# SprayController.net
KiCad netlist of a schematic drawn in EAGLE
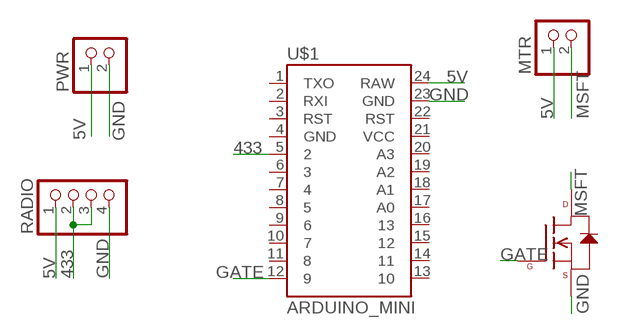
[diagram p0: schematic, sheet 1]

(export (version "E")
  (design (tool "Eeschema 10.0.6"))
  (components
    (comp (ref "MTR")
      (value "PINHD-1X2/90")
      (footprint "eagle-import:1X02_90")
      (libsource (lib "eagle-import") (part "PINHD-1X2/90"))
    )
    (comp (ref "PWR")
      (value "PINHD-1X2/90")
      (footprint "eagle-import:1X02_90")
      (libsource (lib "eagle-import") (part "PINHD-1X2/90"))
    )
    (comp (ref "Q1")
      (value "N-CHANNEL-MOSFET-BSS138")
      (footprint "eagle-import:SOT23-3")
      (libsource (lib "eagle-import") (part "N-CHANNEL-MOSFET-BSS138"))
    )
    (comp (ref "RADIO")
      (value "PINHD-1X4/90")
      (footprint "eagle-import:1X04_90")
      (libsource (lib "eagle-import") (part "PINHD-1X4/90"))
    )
    (comp (ref "U$1")
      (value "ARDUINO_MINI")
      (footprint "eagle-import:ARDUINO_MINI")
      (libsource (lib "eagle-import") (part "ARDUINO_MINI"))
    )
  )
  (nets
    (net (code "1") (name "/5V") (class "Default")
      (node (ref "MTR") (pin "1") (pinfunction "1_1") (pintype "passive"))
      (node (ref "PWR") (pin "1") (pinfunction "1_1") (pintype "passive"))
      (node (ref "RADIO") (pin "1") (pinfunction "1_1") (pintype "passive"))
      (node (ref "U$1") (pin "24") (pinfunction "RAW_24") (pintype "bidirectional"))
    )
    (net (code "2") (name "/433") (class "Default")
      (node (ref "RADIO") (pin "2") (pinfunction "2_2") (pintype "passive"))
      (node (ref "RADIO") (pin "3") (pinfunction "3_3") (pintype "passive"))
      (node (ref "U$1") (pin "5") (pinfunction "2_5") (pintype "bidirectional"))
    )
    (net (code "3") (name "/GATE") (class "Default")
      (node (ref "Q1") (pin "1") (pinfunction "G_1") (pintype "passive"))
      (node (ref "U$1") (pin "12") (pinfunction "9_12") (pintype "bidirectional"))
    )
    (net (code "4") (name "/GND") (class "Default")
      (node (ref "PWR") (pin "2") (pinfunction "2_2") (pintype "passive"))
      (node (ref "Q1") (pin "2") (pinfunction "S_2") (pintype "passive"))
      (node (ref "RADIO") (pin "4") (pinfunction "4_4") (pintype "passive"))
      (node (ref "U$1") (pin "23") (pinfunction "GND_23") (pintype "bidirectional"))
    )
    (net (code "5") (name "/MSFT") (class "Default")
      (node (ref "MTR") (pin "2") (pinfunction "2_2") (pintype "passive"))
      (node (ref "Q1") (pin "3") (pinfunction "D_3") (pintype "passive"))
    )
    (net (code "6") (name "unconnected-(U$1-3-Pad6)") (class "Default")
      (node (ref "U$1") (pin "6") (pinfunction "3_6") (pintype "bidirectional"))
    )
    (net (code "7") (name "unconnected-(U$1-4-Pad7)") (class "Default")
      (node (ref "U$1") (pin "7") (pinfunction "4_7") (pintype "bidirectional"))
    )
    (net (code "8") (name "unconnected-(U$1-5-Pad8)") (class "Default")
      (node (ref "U$1") (pin "8") (pinfunction "5_8") (pintype "bidirectional"))
    )
    (net (code "9") (name "unconnected-(U$1-6-Pad9)") (class "Default")
      (node (ref "U$1") (pin "9") (pinfunction "6_9") (pintype "bidirectional"))
    )
    (net (code "10") (name "unconnected-(U$1-7-Pad10)") (class "Default")
      (node (ref "U$1") (pin "10") (pinfunction "7_10") (pintype "bidirectional"))
    )
    (net (code "11") (name "unconnected-(U$1-8-Pad11)") (class "Default")
      (node (ref "U$1") (pin "11") (pinfunction "8_11") (pintype "bidirectional"))
    )
    (net (code "12") (name "unconnected-(U$1-10-Pad13)") (class "Default")
      (node (ref "U$1") (pin "13") (pinfunction "10_13") (pintype "bidirectional"))
    )
    (net (code "13") (name "unconnected-(U$1-11-Pad14)") (class "Default")
      (node (ref "U$1") (pin "14") (pinfunction "11_14") (pintype "bidirectional"))
    )
    (net (code "14") (name "unconnected-(U$1-12-Pad15)") (class "Default")
      (node (ref "U$1") (pin "15") (pinfunction "12_15") (pintype "bidirectional"))
    )
    (net (code "15") (name "unconnected-(U$1-13-Pad16)") (class "Default")
      (node (ref "U$1") (pin "16") (pinfunction "13_16") (pintype "bidirectional"))
    )
    (net (code "16") (name "unconnected-(U$1-A0-Pad17)") (class "Default")
      (node (ref "U$1") (pin "17") (pinfunction "A0_17") (pintype "bidirectional"))
    )
    (net (code "17") (name "unconnected-(U$1-A1-Pad18)") (class "Default")
      (node (ref "U$1") (pin "18") (pinfunction "A1_18") (pintype "bidirectional"))
    )
    (net (code "18") (name "unconnected-(U$1-A2-Pad19)") (class "Default")
      (node (ref "U$1") (pin "19") (pinfunction "A2_19") (pintype "bidirectional"))
    )
    (net (code "19") (name "unconnected-(U$1-A3-Pad20)") (class "Default")
      (node (ref "U$1") (pin "20") (pinfunction "A3_20") (pintype "bidirectional"))
    )
    (net (code "20") (name "unconnected-(U$1-GND-Pad4)") (class "Default")
      (node (ref "U$1") (pin "4") (pinfunction "GND_4") (pintype "bidirectional"))
    )
    (net (code "21") (name "unconnected-(U$1-RST-Pad3)") (class "Default")
      (node (ref "U$1") (pin "3") (pinfunction "RST_3") (pintype "bidirectional"))
    )
    (net (code "22") (name "unconnected-(U$1-RST-Pad22)") (class "Default")
      (node (ref "U$1") (pin "22") (pinfunction "RST_22") (pintype "bidirectional"))
    )
    (net (code "23") (name "unconnected-(U$1-RXI-Pad2)") (class "Default")
      (node (ref "U$1") (pin "2") (pinfunction "RXI_2") (pintype "bidirectional"))
    )
    (net (code "24") (name "unconnected-(U$1-TXO-Pad1)") (class "Default")
      (node (ref "U$1") (pin "1") (pinfunction "TXO_1") (pintype "bidirectional"))
    )
    (net (code "25") (name "unconnected-(U$1-VCC-Pad21)") (class "Default")
      (node (ref "U$1") (pin "21") (pinfunction "VCC_21") (pintype "bidirectional"))
    )
  )
)
